# Communication.net
KiCad netlist of a schematic drawn in Altium Designer
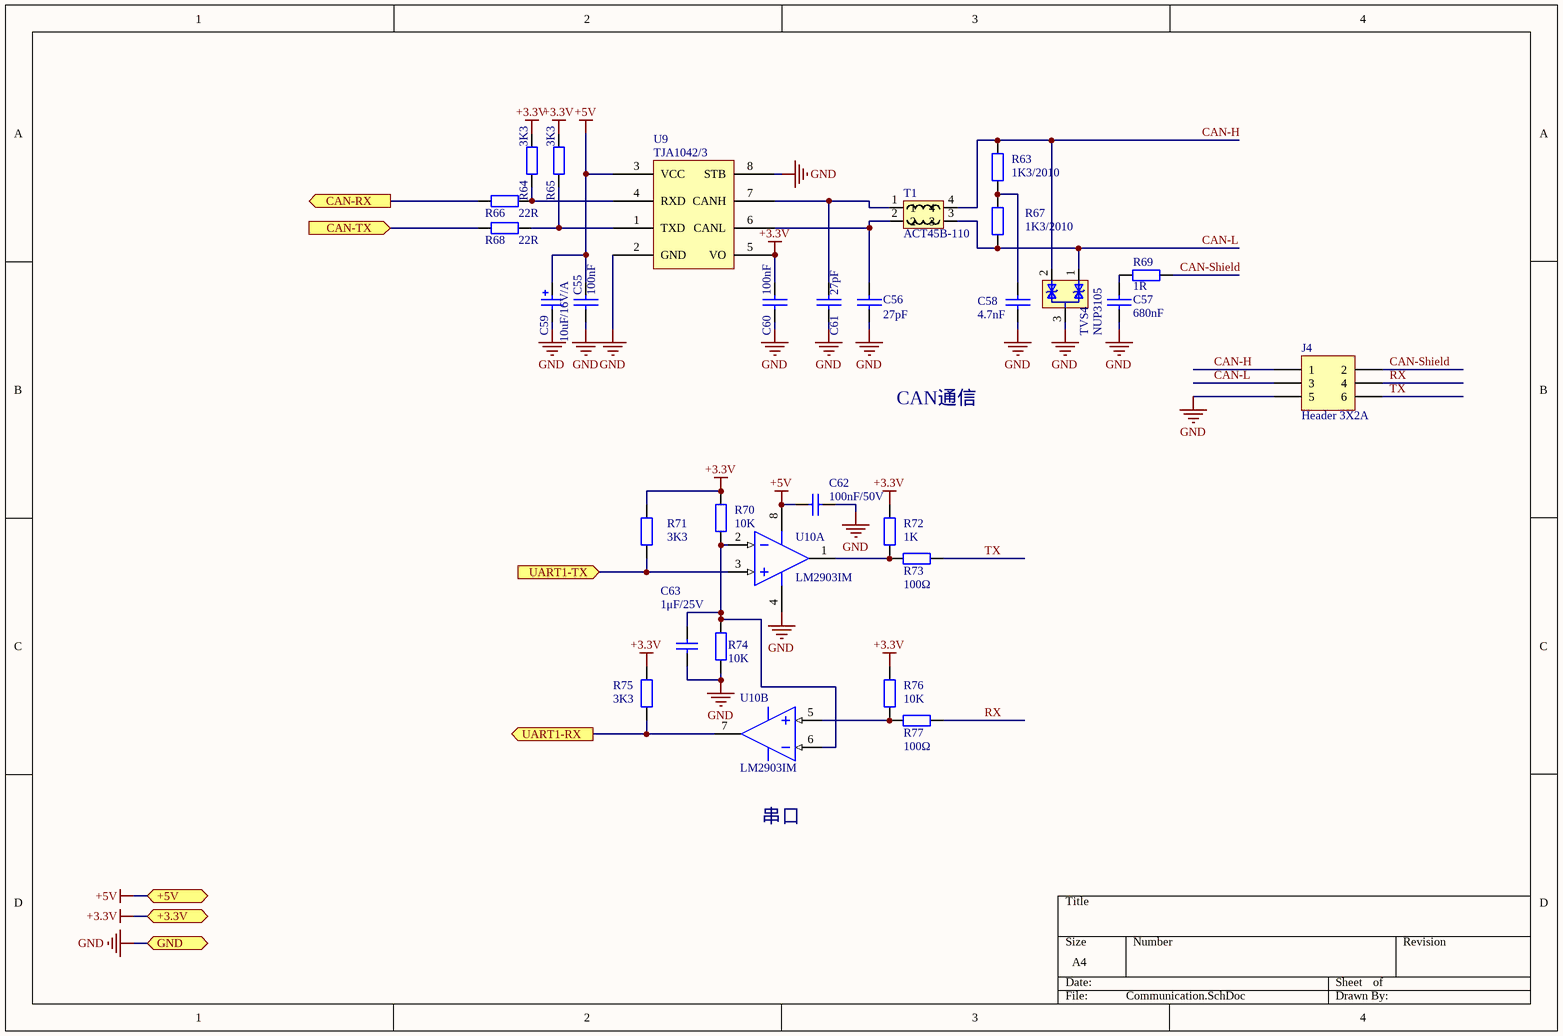
[diagram p0: Communication.SchDoc]

(export (version "E")
  (design (tool "Eeschema 10.0.6"))
  (components
    (comp (ref "C55")
      (value "100nF")
      (footprint "0603")
      (description "Capacitor")
      (libsource (lib "*") (part "CAP"))
    )
    (comp (ref "C56")
      (value "27pF")
      (footprint "0603")
      (description "Capacitor")
      (libsource (lib "*") (part "CAP"))
    )
    (comp (ref "C57")
      (value "680nF")
      (footprint "0805")
      (description "Capacitor")
      (libsource (lib "*") (part "CAP"))
    )
    (comp (ref "C58")
      (value "4.7nF")
      (footprint "0603")
      (description "Capacitor")
      (libsource (lib "*") (part "CAP"))
    )
    (comp (ref "C59")
      (value "10uF/16V/A")
      (footprint "SMD3216-A")
      (libsource (lib "My Component") (part "Cap Pol"))
    )
    (comp (ref "C60")
      (value "100nF")
      (footprint "0603")
      (description "Capacitor")
      (libsource (lib "*") (part "CAP"))
    )
    (comp (ref "C61")
      (value "27pF")
      (footprint "0603")
      (description "Capacitor")
      (libsource (lib "*") (part "CAP"))
    )
    (comp (ref "C62")
      (value "100nF/50V")
      (footprint "0603")
      (description "Capacitor")
      (fields (field (name "PUBLISHER") "Altium Limited"))
      (libsource (lib "Miscellaneous Devices") (part "Cap"))
    )
    (comp (ref "C63")
      (value "1μF/25V")
      (footprint "0603")
      (description "Capacitor")
      (fields (field (name "PUBLISHER") "Altium Limited"))
      (libsource (lib "Miscellaneous Devices") (part "Cap"))
    )
    (comp (ref "J4")
      (value "Header 3X2A")
      (footprint "2.54-6pin-针")
      (description "5569-06,弯角")
      (libsource (lib "JICHENGKU") (part "Header 3X2A"))
    )
    (comp (ref "R63")
      (value "1K3/2010")
      (footprint "2010")
      (description "Resistor")
      (fields (field (name "PUBLISHER") "Altium Limited"))
      (libsource (lib "") (part "Res2_2"))
    )
    (comp (ref "R64")
      (value "3K3")
      (footprint "0603")
      (description "Resistor")
      (fields (field (name "PUBLISHER") "Altium Limited"))
      (libsource (lib "") (part "Res2_1"))
    )
    (comp (ref "R65")
      (value "3K3")
      (footprint "0603")
      (description "Resistor")
      (fields (field (name "PUBLISHER") "Altium Limited"))
      (libsource (lib "") (part "Res2_1"))
    )
    (comp (ref "R66")
      (value "22R")
      (footprint "0603")
      (description "Resistor")
      (fields (field (name "PUBLISHER") "Altium Limited"))
      (libsource (lib "*") (part "Res2"))
    )
    (comp (ref "R67")
      (value "1K3/2010")
      (footprint "2010")
      (description "Resistor")
      (fields (field (name "PUBLISHER") "Altium Limited"))
      (libsource (lib "") (part "Res2_4"))
    )
    (comp (ref "R68")
      (value "22R")
      (footprint "0603")
      (description "Resistor")
      (fields (field (name "PUBLISHER") "Altium Limited"))
      (libsource (lib "*") (part "Res2"))
    )
    (comp (ref "R69")
      (value "1R")
      (footprint "0805")
      (description "Resistor")
      (fields (field (name "PUBLISHER") "Altium Limited"))
      (libsource (lib "") (part "Res2_3"))
    )
    (comp (ref "R70")
      (value "10K")
      (footprint "0603")
      (description "Resistor")
      (fields (field (name "PUBLISHER") "Altium Limited"))
      (libsource (lib "") (part "Res2_4"))
    )
    (comp (ref "R71")
      (value "3K3")
      (footprint "0603")
      (description "Resistor")
      (fields (field (name "PUBLISHER") "Altium Limited"))
      (libsource (lib "") (part "Res2_4"))
    )
    (comp (ref "R72")
      (value "1K")
      (footprint "0603")
      (description "Resistor")
      (fields (field (name "PUBLISHER") "Altium Limited"))
      (libsource (lib "") (part "Res2_4"))
    )
    (comp (ref "R73")
      (value "100Ω")
      (footprint "0805")
      (description "Resistor")
      (fields (field (name "PUBLISHER") "Altium Limited"))
      (libsource (lib "*") (part "Res2"))
    )
    (comp (ref "R74")
      (value "10K")
      (footprint "0603")
      (description "Resistor")
      (fields (field (name "PUBLISHER") "Altium Limited"))
      (libsource (lib "") (part "Res2_4"))
    )
    (comp (ref "R75")
      (value "3K3")
      (footprint "0603")
      (description "Resistor")
      (fields (field (name "PUBLISHER") "Altium Limited"))
      (libsource (lib "") (part "Res2_4"))
    )
    (comp (ref "R76")
      (value "10K")
      (footprint "0603")
      (description "Resistor")
      (fields (field (name "PUBLISHER") "Altium Limited"))
      (libsource (lib "") (part "Res2_4"))
    )
    (comp (ref "R77")
      (value "100Ω")
      (footprint "0805")
      (description "Resistor")
      (fields (field (name "PUBLISHER") "Altium Limited"))
      (libsource (lib "*") (part "Res2"))
    )
    (comp (ref "T1")
      (value "ACT45B-110")
      (footprint "jichengkuPCB:ACT45B")
      (description "晶体共模滤波器")
      (libsource (lib "JICHENGKU") (part "ZJYS81R5-2PL51-G01"))
    )
    (comp (ref "TVS4")
      (value "NUP3105")
      (footprint "SOT-23")
      (libsource (lib "My Component") (part "NUP2105"))
    )
    (comp (ref "U9") (value "TJA1042/3") (footprint "SOP-8") (libsource (lib "Schlib1") (part "TJA1040T")))
    (comp (ref "U10")
      (value "LM2903IM")
      (footprint "SOP-8")
      (description "Low-Power Dual Voltage Comparator")
      (fields (field (name "PUBLISHER") "Altium Limited"))
      (libsource (lib "") (part "LM293AD_1"))
    )
  )
  (nets
    (net (code "1") (name "+3.3V") (class "Default")
      (node (ref "C60") (pin "1") (pinfunction "1_1") (pintype "passive"))
      (node (ref "R64") (pin "2") (pinfunction "2_2") (pintype "passive"))
      (node (ref "R65") (pin "2") (pinfunction "2_2") (pintype "passive"))
      (node (ref "R70") (pin "2") (pinfunction "2_2") (pintype "passive"))
      (node (ref "R71") (pin "2") (pinfunction "2_2") (pintype "passive"))
      (node (ref "R72") (pin "2") (pinfunction "2_2") (pintype "passive"))
      (node (ref "R75") (pin "2") (pinfunction "2_2") (pintype "passive"))
      (node (ref "R76") (pin "2") (pinfunction "2_2") (pintype "passive"))
      (node (ref "U9") (pin "5") (pinfunction "VO_5") (pintype "passive"))
    )
    (net (code "2") (name "+5V") (class "Default")
      (node (ref "C55") (pin "1") (pinfunction "1_1") (pintype "passive"))
      (node (ref "C59") (pin "1") (pinfunction "1_1") (pintype "passive"))
      (node (ref "C62") (pin "2") (pinfunction "2_2") (pintype "passive"))
      (node (ref "U10") (pin "8") (pinfunction "V+_8") (pintype "power_in"))
      (node (ref "U9") (pin "3") (pinfunction "VCC_3") (pintype "passive"))
    )
    (net (code "4") (name "/CAN-H") (class "Default")
      (node (ref "J4") (pin "1") (pinfunction "1_1") (pintype "passive"))
      (node (ref "R63") (pin "1") (pinfunction "1_1") (pintype "passive"))
      (node (ref "T1") (pin "4") (pinfunction "4_4") (pintype "passive"))
      (node (ref "TVS4") (pin "2") (pintype "passive"))
    )
    (net (code "5") (name "/CAN-L") (class "Default")
      (node (ref "J4") (pin "3") (pinfunction "3_3") (pintype "passive"))
      (node (ref "R67") (pin "1") (pinfunction "1_1") (pintype "passive"))
      (node (ref "T1") (pin "3") (pinfunction "3_3") (pintype "passive"))
      (node (ref "TVS4") (pin "1") (pintype "passive"))
    )
    (net (code "6") (name "/CAN-RX") (class "Default")
      (node (ref "R66") (pin "2") (pinfunction "2_2") (pintype "passive"))
    )
    (net (code "7") (name "/CAN-Shield") (class "Default")
      (node (ref "J4") (pin "2") (pinfunction "2_2") (pintype "passive"))
      (node (ref "R69") (pin "2") (pinfunction "2_2") (pintype "passive"))
    )
    (net (code "8") (name "/CAN-TX") (class "Default")
      (node (ref "R68") (pin "2") (pinfunction "2_2") (pintype "passive"))
    )
    (net (code "9") (name "/RX") (class "Default")
      (node (ref "J4") (pin "4") (pinfunction "4_4") (pintype "passive"))
      (node (ref "R77") (pin "1") (pinfunction "1_1") (pintype "passive"))
    )
    (net (code "10") (name "/TX") (class "Default")
      (node (ref "J4") (pin "6") (pinfunction "6_6") (pintype "passive"))
      (node (ref "R73") (pin "1") (pinfunction "1_1") (pintype "passive"))
    )
    (net (code "11") (name "/UART1-RX") (class "Default")
      (node (ref "R75") (pin "1") (pinfunction "1_1") (pintype "passive"))
      (node (ref "U10") (pin "7") (pinfunction "OUT_7") (pintype "open_collector"))
    )
    (net (code "12") (name "/UART1-TX") (class "Default")
      (node (ref "R71") (pin "1") (pinfunction "1_1") (pintype "passive"))
      (node (ref "U10") (pin "3") (pinfunction "IN+_3") (pintype "input"))
    )
    (net (code "13") (name "GND") (class "Default")
      (node (ref "C55") (pin "2") (pinfunction "2_2") (pintype "passive"))
      (node (ref "C56") (pin "1") (pinfunction "1_1") (pintype "passive"))
      (node (ref "C57") (pin "2") (pinfunction "2_2") (pintype "passive"))
      (node (ref "C58") (pin "1") (pinfunction "1_1") (pintype "passive"))
      (node (ref "C59") (pin "2") (pinfunction "2_2") (pintype "passive"))
      (node (ref "C60") (pin "2") (pinfunction "2_2") (pintype "passive"))
      (node (ref "C61") (pin "1") (pinfunction "1_1") (pintype "passive"))
      (node (ref "C62") (pin "1") (pinfunction "1_1") (pintype "passive"))
      (node (ref "C63") (pin "1") (pinfunction "1_1") (pintype "passive"))
      (node (ref "J4") (pin "5") (pinfunction "5_5") (pintype "passive"))
      (node (ref "R74") (pin "1") (pinfunction "1_1") (pintype "passive"))
      (node (ref "TVS4") (pin "3") (pintype "passive"))
      (node (ref "U10") (pin "4") (pinfunction "V-_4") (pintype "power_in"))
      (node (ref "U9") (pin "2") (pinfunction "GND_2") (pintype "passive"))
      (node (ref "U9") (pin "8") (pinfunction "STB_8") (pintype "passive"))
    )
    (net (code "14") (name "Net-(C57-Pad1)") (class "Default")
      (node (ref "C57") (pin "1") (pinfunction "1_1") (pintype "passive"))
      (node (ref "R69") (pin "1") (pinfunction "1_1") (pintype "passive"))
    )
    (net (code "15") (name "Net-(C58-Pad2)") (class "Default")
      (node (ref "C58") (pin "2") (pinfunction "2_2") (pintype "passive"))
      (node (ref "R63") (pin "2") (pinfunction "2_2") (pintype "passive"))
      (node (ref "R67") (pin "2") (pinfunction "2_2") (pintype "passive"))
    )
    (net (code "16") (name "Net-(U9-CANH)") (class "Default")
      (node (ref "C61") (pin "2") (pinfunction "2_2") (pintype "passive"))
      (node (ref "T1") (pin "1") (pinfunction "1_1") (pintype "passive"))
      (node (ref "U9") (pin "7") (pinfunction "CANH_7") (pintype "passive"))
    )
    (net (code "17") (name "Net-(U9-CANL)") (class "Default")
      (node (ref "C56") (pin "2") (pinfunction "2_2") (pintype "passive"))
      (node (ref "T1") (pin "2") (pinfunction "2_2") (pintype "passive"))
      (node (ref "U9") (pin "6") (pinfunction "CANL_6") (pintype "passive"))
    )
    (net (code "18") (name "Net-(U9-RXD)") (class "Default")
      (node (ref "R64") (pin "1") (pinfunction "1_1") (pintype "passive"))
      (node (ref "R66") (pin "1") (pinfunction "1_1") (pintype "passive"))
      (node (ref "U9") (pin "4") (pinfunction "RXD_4") (pintype "passive"))
    )
    (net (code "19") (name "Net-(U9-TXD)") (class "Default")
      (node (ref "R65") (pin "1") (pinfunction "1_1") (pintype "passive"))
      (node (ref "R68") (pin "1") (pinfunction "1_1") (pintype "passive"))
      (node (ref "U9") (pin "1") (pinfunction "TXD_1") (pintype "passive"))
    )
    (net (code "20") (name "Net-(U10A-IN-)") (class "Default")
      (node (ref "C63") (pin "2") (pinfunction "2_2") (pintype "passive"))
      (node (ref "R70") (pin "1") (pinfunction "1_1") (pintype "passive"))
      (node (ref "R74") (pin "2") (pinfunction "2_2") (pintype "passive"))
      (node (ref "U10") (pin "2") (pinfunction "IN-_2") (pintype "input"))
      (node (ref "U10") (pin "6") (pinfunction "IN-_6") (pintype "input"))
    )
    (net (code "21") (name "Net-(U10A-OUT)") (class "Default")
      (node (ref "R72") (pin "1") (pinfunction "1_1") (pintype "passive"))
      (node (ref "R73") (pin "2") (pinfunction "2_2") (pintype "passive"))
      (node (ref "U10") (pin "1") (pinfunction "OUT_1") (pintype "open_collector"))
    )
    (net (code "22") (name "Net-(U10B-IN+)") (class "Default")
      (node (ref "R76") (pin "1") (pinfunction "1_1") (pintype "passive"))
      (node (ref "R77") (pin "2") (pinfunction "2_2") (pintype "passive"))
      (node (ref "U10") (pin "5") (pinfunction "IN+_5") (pintype "input"))
    )
    (net (code "23") (name "V+") (class "Default")
      (node (ref "U10") (pin "8") (pinfunction "V+_8") (pintype "power_in"))
    )
    (net (code "24") (name "V-") (class "Default")
      (node (ref "U10") (pin "4") (pinfunction "V-_4") (pintype "power_in"))
    )
  )
)
